# TConn2.net
KiCad netlist of a schematic drawn in EAGLE
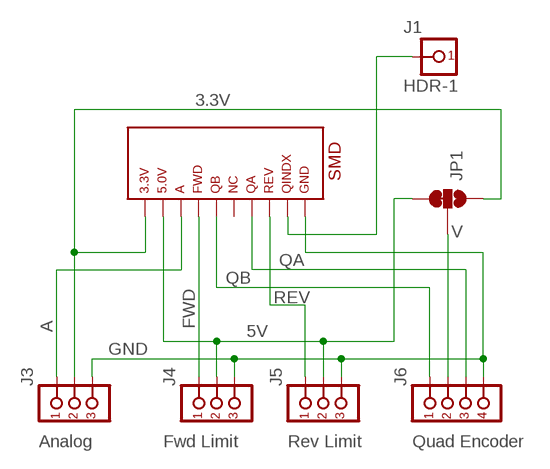
[diagram p0: schematic, sheet 1]

(export (version "E")
  (design (tool "Eeschema 10.0.6"))
  (components
    (comp (ref "J1")
      (value "HDR-1")
      (footprint "eagle-import:POST1X1")
      (libsource (lib "eagle-import") (part "HDR-1"))
    )
    (comp (ref "J3")
      (value "HDR-3")
      (footprint "eagle-import:POST1X3")
      (libsource (lib "eagle-import") (part "HDR-3"))
    )
    (comp (ref "J4")
      (value "HDR-3NYLON-RT-3")
      (footprint "eagle-import:NYLON-RT-3")
      (libsource (lib "eagle-import") (part "HDR-3NYLON-RT-3"))
    )
    (comp (ref "J5")
      (value "HDR-3NYLON-RT-3")
      (footprint "eagle-import:NYLON-RT-3")
      (libsource (lib "eagle-import") (part "HDR-3NYLON-RT-3"))
    )
    (comp (ref "J6")
      (value "HDR-4NYLON-RT-4")
      (footprint "eagle-import:NYLON-RT-4")
      (libsource (lib "eagle-import") (part "HDR-4NYLON-RT-4"))
    )
    (comp (ref "JP1")
      (value "JUMPER-SMT_3_1-NC_TRACE_SILK")
      (footprint "eagle-import:SMT-JUMPER_3_1-NC_TRACE_SILK")
      (libsource (lib "eagle-import") (part "JUMPER-SMT_3_1-NC_TRACE_SILK"))
    )
    (comp (ref "T1")
      (value "TANON-HDR-THSMD-MOUNT")
      (footprint "eagle-import:TALON-5X2-SMD2")
      (libsource (lib "eagle-import") (part "TANON-HDR-THSMD-MOUNT"))
    )
  )
  (nets
    (net (code "1") (name "/3.3V") (class "Default")
      (node (ref "J3") (pin "2") (pinfunction "2_2") (pintype "passive"))
      (node (ref "JP1") (pin "1") (pinfunction "1_1") (pintype "passive"))
      (node (ref "T1") (pin "P$1") (pinfunction "P$1_P$1") (pintype "bidirectional"))
    )
    (net (code "2") (name "/5V") (class "Default")
      (node (ref "J4") (pin "P$2") (pinfunction "2_P$2") (pintype "passive"))
      (node (ref "J5") (pin "P$2") (pinfunction "2_P$2") (pintype "passive"))
      (node (ref "JP1") (pin "3") (pinfunction "3_3") (pintype "passive"))
      (node (ref "T1") (pin "P$2") (pinfunction "P$2_P$2") (pintype "bidirectional"))
    )
    (net (code "3") (name "/A") (class "Default")
      (node (ref "J3") (pin "1") (pinfunction "1_1") (pintype "passive"))
      (node (ref "T1") (pin "P$3") (pinfunction "P$3_P$3") (pintype "bidirectional"))
    )
    (net (code "4") (name "/FWD") (class "Default")
      (node (ref "J4") (pin "P$1") (pinfunction "1_P$1") (pintype "passive"))
      (node (ref "T1") (pin "P$4") (pinfunction "P$4_P$4") (pintype "bidirectional"))
    )
    (net (code "5") (name "/GND") (class "Default")
      (node (ref "J3") (pin "3") (pinfunction "3_3") (pintype "passive"))
      (node (ref "J4") (pin "P$3") (pinfunction "3_P$3") (pintype "passive"))
      (node (ref "J5") (pin "P$3") (pinfunction "3_P$3") (pintype "passive"))
      (node (ref "J6") (pin "P$4") (pinfunction "4_P$4") (pintype "passive"))
      (node (ref "T1") (pin "P$10") (pinfunction "P$10_P$10") (pintype "bidirectional"))
    )
    (net (code "6") (name "/QA") (class "Default")
      (node (ref "J6") (pin "P$3") (pinfunction "3_P$3") (pintype "passive"))
      (node (ref "T1") (pin "P$7") (pinfunction "P$7_P$7") (pintype "bidirectional"))
    )
    (net (code "7") (name "/QB") (class "Default")
      (node (ref "J6") (pin "P$1") (pinfunction "1_P$1") (pintype "passive"))
      (node (ref "T1") (pin "P$5") (pinfunction "P$5_P$5") (pintype "bidirectional"))
    )
    (net (code "8") (name "/REV") (class "Default")
      (node (ref "J5") (pin "P$1") (pinfunction "1_P$1") (pintype "passive"))
      (node (ref "T1") (pin "P$8") (pinfunction "P$8_P$8") (pintype "bidirectional"))
    )
    (net (code "9") (name "/V") (class "Default")
      (node (ref "J6") (pin "P$2") (pinfunction "2_P$2") (pintype "passive"))
      (node (ref "JP1") (pin "2") (pinfunction "2_2") (pintype "passive"))
    )
    (net (code "10") (name "Net-(J1-Pad1)") (class "Default")
      (node (ref "J1") (pin "1") (pinfunction "1_1") (pintype "passive"))
      (node (ref "T1") (pin "P$9") (pinfunction "P$9_P$9") (pintype "bidirectional"))
    )
    (net (code "11") (name "unconnected-(T1-PadP$6)") (class "Default")
      (node (ref "T1") (pin "P$6") (pinfunction "P$6_P$6") (pintype "bidirectional"))
    )
  )
)
